# Power_Cond_2.net
KiCad netlist of a schematic drawn in EAGLE
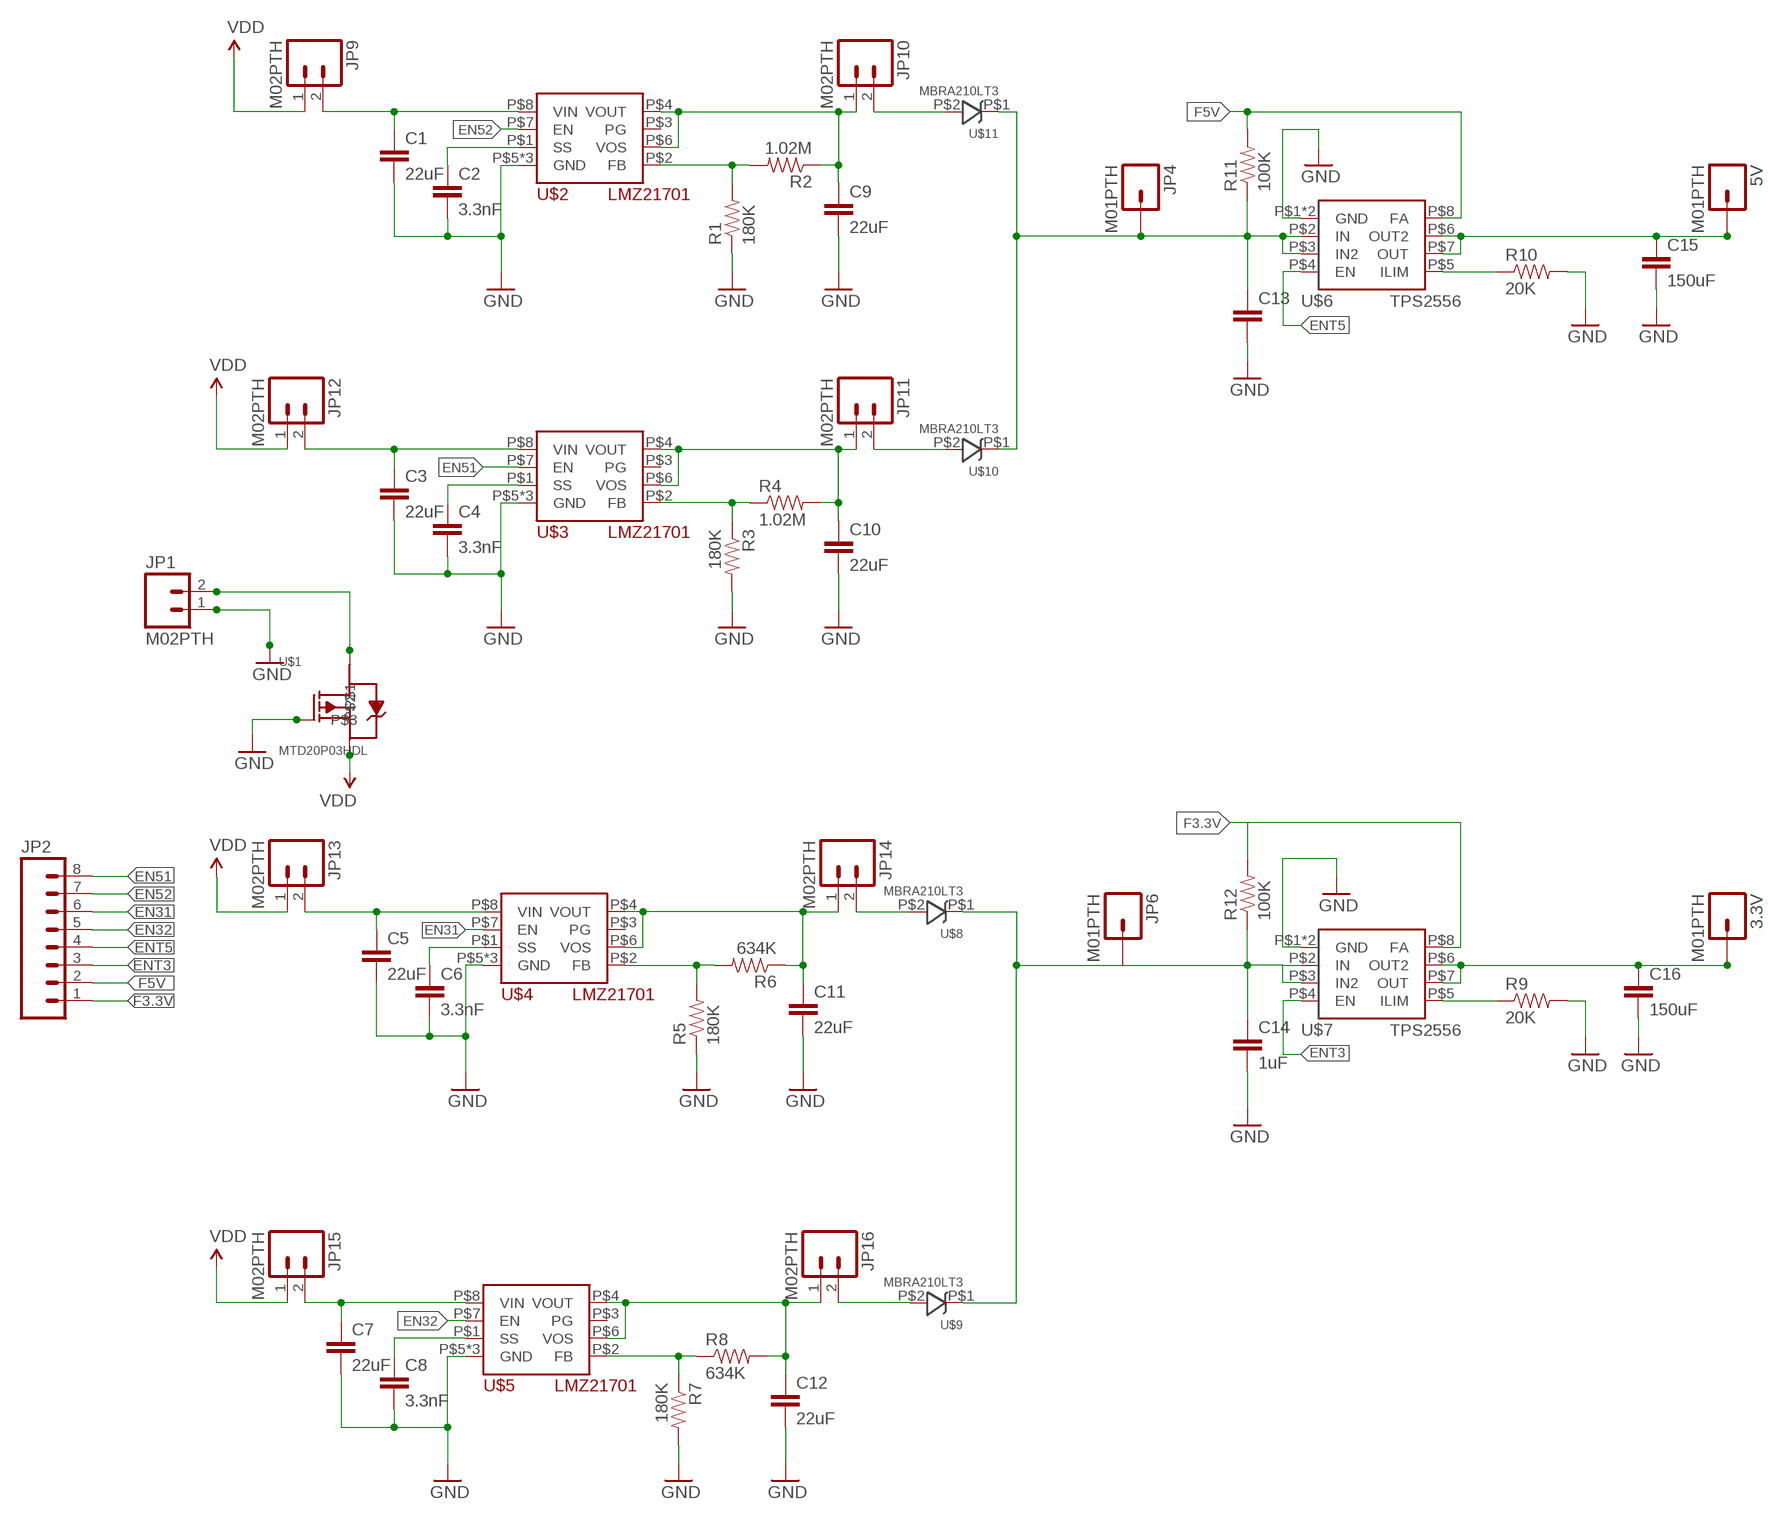
[diagram p0: schematic, sheet 1]

(export (version "E")
  (design (tool "Eeschema 10.0.6"))
  (components
    (comp (ref "3.3V")
      (value "M01PTH")
      (footprint "eagle-import:1X01")
      (libsource (lib "eagle-import") (part "M01PTH"))
    )
    (comp (ref "5V")
      (value "M01PTH")
      (footprint "eagle-import:1X01")
      (libsource (lib "eagle-import") (part "M01PTH"))
    )
    (comp (ref "C1")
      (value "22uF")
      (footprint "eagle-import:0603-CAP")
      (libsource (lib "eagle-import") (part "CAP0603-CAP"))
    )
    (comp (ref "C2")
      (value "3.3nF")
      (footprint "eagle-import:0603-CAP")
      (libsource (lib "eagle-import") (part "CAP0603-CAP"))
    )
    (comp (ref "C3")
      (value "22uF")
      (footprint "eagle-import:0603-CAP")
      (libsource (lib "eagle-import") (part "CAP0603-CAP"))
    )
    (comp (ref "C4")
      (value "3.3nF")
      (footprint "eagle-import:0603-CAP")
      (libsource (lib "eagle-import") (part "CAP0603-CAP"))
    )
    (comp (ref "C5")
      (value "22uF")
      (footprint "eagle-import:0603-CAP")
      (libsource (lib "eagle-import") (part "CAP0603-CAP"))
    )
    (comp (ref "C6")
      (value "3.3nF")
      (footprint "eagle-import:0603-CAP")
      (libsource (lib "eagle-import") (part "CAP0603-CAP"))
    )
    (comp (ref "C7")
      (value "22uF")
      (footprint "eagle-import:0603-CAP")
      (libsource (lib "eagle-import") (part "CAP0603-CAP"))
    )
    (comp (ref "C8")
      (value "3.3nF")
      (footprint "eagle-import:0603-CAP")
      (libsource (lib "eagle-import") (part "CAP0603-CAP"))
    )
    (comp (ref "C9")
      (value "22uF")
      (footprint "eagle-import:0603-CAP")
      (libsource (lib "eagle-import") (part "CAP0603-CAP"))
    )
    (comp (ref "C10")
      (value "22uF")
      (footprint "eagle-import:0603-CAP")
      (libsource (lib "eagle-import") (part "CAP0603-CAP"))
    )
    (comp (ref "C11")
      (value "22uF")
      (footprint "eagle-import:0603-CAP")
      (libsource (lib "eagle-import") (part "CAP0603-CAP"))
    )
    (comp (ref "C12")
      (value "22uF")
      (footprint "eagle-import:0603-CAP")
      (libsource (lib "eagle-import") (part "CAP0603-CAP"))
    )
    (comp (ref "C13")
      (value "CAP0603-CAP")
      (footprint "eagle-import:0603-CAP")
      (libsource (lib "eagle-import") (part "CAP0603-CAP"))
    )
    (comp (ref "C14")
      (value "1uF")
      (footprint "eagle-import:0603-CAP")
      (libsource (lib "eagle-import") (part "CAP0603-CAP"))
    )
    (comp (ref "C15")
      (value "150uF")
      (footprint "eagle-import:1206")
      (libsource (lib "eagle-import") (part "CAP1206"))
    )
    (comp (ref "C16")
      (value "150uF")
      (footprint "eagle-import:1206")
      (libsource (lib "eagle-import") (part "CAP1206"))
    )
    (comp (ref "JP1")
      (value "M02PTH")
      (footprint "eagle-import:1X02")
      (libsource (lib "eagle-import") (part "M02PTH"))
    )
    (comp (ref "JP2")
      (value "M08")
      (footprint "eagle-import:1X08_ROUND")
      (libsource (lib "eagle-import") (part "M08"))
    )
    (comp (ref "JP4")
      (value "M01PTH")
      (footprint "eagle-import:1X01")
      (libsource (lib "eagle-import") (part "M01PTH"))
    )
    (comp (ref "JP6")
      (value "M01PTH")
      (footprint "eagle-import:1X01")
      (libsource (lib "eagle-import") (part "M01PTH"))
    )
    (comp (ref "JP9")
      (value "M02PTH")
      (footprint "eagle-import:1X02")
      (libsource (lib "eagle-import") (part "M02PTH"))
    )
    (comp (ref "JP10")
      (value "M02PTH")
      (footprint "eagle-import:1X02")
      (libsource (lib "eagle-import") (part "M02PTH"))
    )
    (comp (ref "JP11")
      (value "M02PTH")
      (footprint "eagle-import:1X02")
      (libsource (lib "eagle-import") (part "M02PTH"))
    )
    (comp (ref "JP12")
      (value "M02PTH")
      (footprint "eagle-import:1X02")
      (libsource (lib "eagle-import") (part "M02PTH"))
    )
    (comp (ref "JP13")
      (value "M02PTH")
      (footprint "eagle-import:1X02")
      (libsource (lib "eagle-import") (part "M02PTH"))
    )
    (comp (ref "JP14")
      (value "M02PTH")
      (footprint "eagle-import:1X02")
      (libsource (lib "eagle-import") (part "M02PTH"))
    )
    (comp (ref "JP15")
      (value "M02PTH")
      (footprint "eagle-import:1X02")
      (libsource (lib "eagle-import") (part "M02PTH"))
    )
    (comp (ref "JP16")
      (value "M02PTH")
      (footprint "eagle-import:1X02")
      (libsource (lib "eagle-import") (part "M02PTH"))
    )
    (comp (ref "R1")
      (value "180K")
      (footprint "eagle-import:0603-RES")
      (libsource (lib "eagle-import") (part "RESISTOR0603-RES"))
    )
    (comp (ref "R2")
      (value "1.02M")
      (footprint "eagle-import:0603-RES")
      (libsource (lib "eagle-import") (part "RESISTOR0603-RES"))
    )
    (comp (ref "R3")
      (value "180K")
      (footprint "eagle-import:0603-RES")
      (libsource (lib "eagle-import") (part "RESISTOR0603-RES"))
    )
    (comp (ref "R4")
      (value "1.02M")
      (footprint "eagle-import:0603-RES")
      (libsource (lib "eagle-import") (part "RESISTOR0603-RES"))
    )
    (comp (ref "R5")
      (value "180K")
      (footprint "eagle-import:0603-RES")
      (libsource (lib "eagle-import") (part "RESISTOR0603-RES"))
    )
    (comp (ref "R6")
      (value "634K")
      (footprint "eagle-import:0603-RES")
      (libsource (lib "eagle-import") (part "RESISTOR0603-RES"))
    )
    (comp (ref "R7")
      (value "180K")
      (footprint "eagle-import:0603-RES")
      (libsource (lib "eagle-import") (part "RESISTOR0603-RES"))
    )
    (comp (ref "R8")
      (value "634K")
      (footprint "eagle-import:0603-RES")
      (libsource (lib "eagle-import") (part "RESISTOR0603-RES"))
    )
    (comp (ref "R9")
      (value "20K")
      (footprint "eagle-import:0603-RES")
      (libsource (lib "eagle-import") (part "RESISTOR0603-RES"))
    )
    (comp (ref "R10")
      (value "20K")
      (footprint "eagle-import:0603-RES")
      (libsource (lib "eagle-import") (part "RESISTOR0603-RES"))
    )
    (comp (ref "R11")
      (value "100K")
      (footprint "eagle-import:0603-RES")
      (libsource (lib "eagle-import") (part "RESISTOR0603-RES"))
    )
    (comp (ref "R12")
      (value "100K")
      (footprint "eagle-import:0603-RES")
      (libsource (lib "eagle-import") (part "RESISTOR0603-RES"))
    )
    (comp (ref "U$1")
      (value "MTD20P03HDL")
      (footprint "eagle-import:DPAK_369C_SMD")
      (libsource (lib "eagle-import") (part "MTD20P03HDL"))
    )
    (comp (ref "U$2")
      (value "LMZ21701")
      (footprint "eagle-import:LMZ21701")
      (libsource (lib "eagle-import") (part "LMZ21701"))
    )
    (comp (ref "U$3")
      (value "LMZ21701")
      (footprint "eagle-import:LMZ21701")
      (libsource (lib "eagle-import") (part "LMZ21701"))
    )
    (comp (ref "U$4")
      (value "LMZ21701")
      (footprint "eagle-import:LMZ21701")
      (libsource (lib "eagle-import") (part "LMZ21701"))
    )
    (comp (ref "U$5")
      (value "LMZ21701")
      (footprint "eagle-import:LMZ21701")
      (libsource (lib "eagle-import") (part "LMZ21701"))
    )
    (comp (ref "U$6")
      (value "TPS2556")
      (footprint "eagle-import:TPS2556")
      (libsource (lib "eagle-import") (part "TPS2556"))
    )
    (comp (ref "U$7")
      (value "TPS2556")
      (footprint "eagle-import:TPS2556")
      (libsource (lib "eagle-import") (part "TPS2556"))
    )
    (comp (ref "U$8")
      (value "MBRA210LT3")
      (footprint "eagle-import:DO-214AC-SMA")
      (libsource (lib "eagle-import") (part "MBRA210LT3"))
    )
    (comp (ref "U$9")
      (value "MBRA210LT3")
      (footprint "eagle-import:DO-214AC-SMA")
      (libsource (lib "eagle-import") (part "MBRA210LT3"))
    )
    (comp (ref "U$10")
      (value "MBRA210LT3")
      (footprint "eagle-import:DO-214AC-SMA")
      (libsource (lib "eagle-import") (part "MBRA210LT3"))
    )
    (comp (ref "U$11")
      (value "MBRA210LT3")
      (footprint "eagle-import:DO-214AC-SMA")
      (libsource (lib "eagle-import") (part "MBRA210LT3"))
    )
  )
  (nets
    (net (code "1") (name "/EN31") (class "Default")
      (node (ref "C5") (pin "1") (pinfunction "1_1") (pintype "passive"))
      (node (ref "JP13") (pin "2") (pinfunction "2_2") (pintype "passive"))
      (node (ref "JP2") (pin "6") (pinfunction "6_6") (pintype "passive"))
      (node (ref "U$4") (pin "P$7") (pinfunction "EN_P$7") (pintype "bidirectional"))
      (node (ref "U$4") (pin "P$8") (pinfunction "VIN_P$8") (pintype "bidirectional"))
    )
    (net (code "2") (name "/EN32") (class "Default")
      (node (ref "JP2") (pin "5") (pinfunction "5_5") (pintype "passive"))
      (node (ref "U$5") (pin "P$7") (pinfunction "EN_P$7") (pintype "bidirectional"))
    )
    (net (code "3") (name "/EN51") (class "Default")
      (node (ref "JP2") (pin "8") (pinfunction "8_8") (pintype "passive"))
      (node (ref "U$3") (pin "P$7") (pinfunction "EN_P$7") (pintype "bidirectional"))
    )
    (net (code "4") (name "/EN52") (class "Default")
      (node (ref "JP2") (pin "7") (pinfunction "7_7") (pintype "passive"))
      (node (ref "U$2") (pin "P$7") (pinfunction "EN_P$7") (pintype "bidirectional"))
    )
    (net (code "5") (name "/ENT3") (class "Default")
      (node (ref "JP2") (pin "3") (pinfunction "3_3") (pintype "passive"))
      (node (ref "U$7") (pin "P$4") (pinfunction "EN_P$4") (pintype "bidirectional"))
    )
    (net (code "6") (name "/ENT5") (class "Default")
      (node (ref "JP2") (pin "4") (pinfunction "4_4") (pintype "passive"))
      (node (ref "U$6") (pin "P$4") (pinfunction "EN_P$4") (pintype "bidirectional"))
    )
    (net (code "7") (name "/F3.3V") (class "Default")
      (node (ref "JP2") (pin "1") (pinfunction "1_1") (pintype "passive"))
      (node (ref "R12") (pin "2") (pinfunction "2_2") (pintype "passive"))
      (node (ref "U$7") (pin "P$8") (pinfunction "FA_P$8") (pintype "bidirectional"))
    )
    (net (code "8") (name "/F5V") (class "Default")
      (node (ref "JP2") (pin "2") (pinfunction "2_2") (pintype "passive"))
      (node (ref "R11") (pin "2") (pinfunction "2_2") (pintype "passive"))
      (node (ref "U$6") (pin "P$8") (pinfunction "FA_P$8") (pintype "bidirectional"))
    )
    (net (code "9") (name "GND") (class "Default")
      (node (ref "C1") (pin "2") (pinfunction "2_2") (pintype "passive"))
      (node (ref "C10") (pin "2") (pinfunction "2_2") (pintype "passive"))
      (node (ref "C11") (pin "2") (pinfunction "2_2") (pintype "passive"))
      (node (ref "C12") (pin "2") (pinfunction "2_2") (pintype "passive"))
      (node (ref "C13") (pin "2") (pinfunction "2_2") (pintype "passive"))
      (node (ref "C14") (pin "2") (pinfunction "2_2") (pintype "passive"))
      (node (ref "C15") (pin "2") (pinfunction "2_2") (pintype "passive"))
      (node (ref "C16") (pin "2") (pinfunction "2_2") (pintype "passive"))
      (node (ref "C2") (pin "2") (pinfunction "2_2") (pintype "passive"))
      (node (ref "C3") (pin "2") (pinfunction "2_2") (pintype "passive"))
      (node (ref "C4") (pin "2") (pinfunction "2_2") (pintype "passive"))
      (node (ref "C5") (pin "2") (pinfunction "2_2") (pintype "passive"))
      (node (ref "C6") (pin "2") (pinfunction "2_2") (pintype "passive"))
      (node (ref "C7") (pin "2") (pinfunction "2_2") (pintype "passive"))
      (node (ref "C8") (pin "2") (pinfunction "2_2") (pintype "passive"))
      (node (ref "C9") (pin "2") (pinfunction "2_2") (pintype "passive"))
      (node (ref "JP1") (pin "1") (pinfunction "1_1") (pintype "passive"))
      (node (ref "R1") (pin "1") (pinfunction "1_1") (pintype "passive"))
      (node (ref "R10") (pin "2") (pinfunction "2_2") (pintype "passive"))
      (node (ref "R3") (pin "2") (pinfunction "2_2") (pintype "passive"))
      (node (ref "R5") (pin "1") (pinfunction "1_1") (pintype "passive"))
      (node (ref "R7") (pin "2") (pinfunction "2_2") (pintype "passive"))
      (node (ref "R9") (pin "2") (pinfunction "2_2") (pintype "passive"))
      (node (ref "U$1") (pin "P$3") (pinfunction "P$3_P$3") (pintype "bidirectional"))
      (node (ref "U$2") (pin "P$10") (pinfunction "GND_P$10") (pintype "bidirectional"))
      (node (ref "U$2") (pin "P$5") (pinfunction "GND_P$5") (pintype "bidirectional"))
      (node (ref "U$2") (pin "P$9") (pinfunction "GND_P$9") (pintype "bidirectional"))
      (node (ref "U$3") (pin "P$10") (pinfunction "GND_P$10") (pintype "bidirectional"))
      (node (ref "U$3") (pin "P$5") (pinfunction "GND_P$5") (pintype "bidirectional"))
      (node (ref "U$3") (pin "P$9") (pinfunction "GND_P$9") (pintype "bidirectional"))
      (node (ref "U$4") (pin "P$10") (pinfunction "GND_P$10") (pintype "bidirectional"))
      (node (ref "U$4") (pin "P$5") (pinfunction "GND_P$5") (pintype "bidirectional"))
      (node (ref "U$4") (pin "P$9") (pinfunction "GND_P$9") (pintype "bidirectional"))
      (node (ref "U$5") (pin "P$10") (pinfunction "GND_P$10") (pintype "bidirectional"))
      (node (ref "U$5") (pin "P$5") (pinfunction "GND_P$5") (pintype "bidirectional"))
      (node (ref "U$5") (pin "P$9") (pinfunction "GND_P$9") (pintype "bidirectional"))
      (node (ref "U$6") (pin "P$1") (pinfunction "GND_P$1") (pintype "bidirectional"))
      (node (ref "U$6") (pin "P$9") (pinfunction "GND_P$9") (pintype "bidirectional"))
      (node (ref "U$7") (pin "P$1") (pinfunction "GND_P$1") (pintype "bidirectional"))
      (node (ref "U$7") (pin "P$9") (pinfunction "GND_P$9") (pintype "bidirectional"))
    )
    (net (code "10") (name "Net-(JP10-Pad2)") (class "Default")
      (node (ref "JP10") (pin "2") (pinfunction "2_2") (pintype "passive"))
      (node (ref "U$11") (pin "P$2") (pinfunction "P$2_P$2") (pintype "bidirectional"))
    )
    (net (code "11") (name "Net-(JP11-Pad2)") (class "Default")
      (node (ref "JP11") (pin "2") (pinfunction "2_2") (pintype "passive"))
      (node (ref "U$10") (pin "P$2") (pinfunction "P$2_P$2") (pintype "bidirectional"))
    )
    (net (code "12") (name "Net-(JP14-Pad2)") (class "Default")
      (node (ref "JP14") (pin "2") (pinfunction "2_2") (pintype "passive"))
      (node (ref "U$8") (pin "P$2") (pinfunction "P$2_P$2") (pintype "bidirectional"))
    )
    (net (code "13") (name "Net-(JP16-Pad2)") (class "Default")
      (node (ref "JP16") (pin "2") (pinfunction "2_2") (pintype "passive"))
      (node (ref "U$9") (pin "P$2") (pinfunction "P$2_P$2") (pintype "bidirectional"))
    )
    (net (code "14") (name "Net-(U$2-FB)") (class "Default")
      (node (ref "R1") (pin "2") (pinfunction "2_2") (pintype "passive"))
      (node (ref "R2") (pin "2") (pinfunction "2_2") (pintype "passive"))
      (node (ref "U$2") (pin "P$2") (pinfunction "FB_P$2") (pintype "bidirectional"))
    )
    (net (code "15") (name "Net-(U$2-SS)") (class "Default")
      (node (ref "C2") (pin "1") (pinfunction "1_1") (pintype "passive"))
      (node (ref "U$2") (pin "P$1") (pinfunction "SS_P$1") (pintype "bidirectional"))
    )
    (net (code "16") (name "Net-(U$2-VIN)") (class "Default")
      (node (ref "C1") (pin "1") (pinfunction "1_1") (pintype "passive"))
      (node (ref "JP9") (pin "2") (pinfunction "2_2") (pintype "passive"))
      (node (ref "U$2") (pin "P$8") (pinfunction "VIN_P$8") (pintype "bidirectional"))
    )
    (net (code "17") (name "Net-(U$2-VOS)") (class "Default")
      (node (ref "C9") (pin "1") (pinfunction "1_1") (pintype "passive"))
      (node (ref "JP10") (pin "1") (pinfunction "1_1") (pintype "passive"))
      (node (ref "R2") (pin "1") (pinfunction "1_1") (pintype "passive"))
      (node (ref "U$2") (pin "P$4") (pinfunction "VOUT_P$4") (pintype "bidirectional"))
      (node (ref "U$2") (pin "P$6") (pinfunction "VOS_P$6") (pintype "bidirectional"))
    )
    (net (code "18") (name "Net-(U$3-FB)") (class "Default")
      (node (ref "R3") (pin "1") (pinfunction "1_1") (pintype "passive"))
      (node (ref "R4") (pin "1") (pinfunction "1_1") (pintype "passive"))
      (node (ref "U$3") (pin "P$2") (pinfunction "FB_P$2") (pintype "bidirectional"))
    )
    (net (code "19") (name "Net-(U$3-SS)") (class "Default")
      (node (ref "C4") (pin "1") (pinfunction "1_1") (pintype "passive"))
      (node (ref "U$3") (pin "P$1") (pinfunction "SS_P$1") (pintype "bidirectional"))
    )
    (net (code "20") (name "Net-(U$3-VIN)") (class "Default")
      (node (ref "C3") (pin "1") (pinfunction "1_1") (pintype "passive"))
      (node (ref "JP12") (pin "2") (pinfunction "2_2") (pintype "passive"))
      (node (ref "U$3") (pin "P$8") (pinfunction "VIN_P$8") (pintype "bidirectional"))
    )
    (net (code "21") (name "Net-(U$3-VOS)") (class "Default")
      (node (ref "C10") (pin "1") (pinfunction "1_1") (pintype "passive"))
      (node (ref "JP11") (pin "1") (pinfunction "1_1") (pintype "passive"))
      (node (ref "R4") (pin "2") (pinfunction "2_2") (pintype "passive"))
      (node (ref "U$3") (pin "P$4") (pinfunction "VOUT_P$4") (pintype "bidirectional"))
      (node (ref "U$3") (pin "P$6") (pinfunction "VOS_P$6") (pintype "bidirectional"))
    )
    (net (code "22") (name "Net-(U$4-FB)") (class "Default")
      (node (ref "R5") (pin "2") (pinfunction "2_2") (pintype "passive"))
      (node (ref "R6") (pin "2") (pinfunction "2_2") (pintype "passive"))
      (node (ref "U$4") (pin "P$2") (pinfunction "FB_P$2") (pintype "bidirectional"))
    )
    (net (code "23") (name "Net-(U$4-SS)") (class "Default")
      (node (ref "C6") (pin "1") (pinfunction "1_1") (pintype "passive"))
      (node (ref "U$4") (pin "P$1") (pinfunction "SS_P$1") (pintype "bidirectional"))
    )
    (net (code "24") (name "Net-(U$4-VOS)") (class "Default")
      (node (ref "C11") (pin "1") (pinfunction "1_1") (pintype "passive"))
      (node (ref "JP14") (pin "1") (pinfunction "1_1") (pintype "passive"))
      (node (ref "R6") (pin "1") (pinfunction "1_1") (pintype "passive"))
      (node (ref "U$4") (pin "P$4") (pinfunction "VOUT_P$4") (pintype "bidirectional"))
      (node (ref "U$4") (pin "P$6") (pinfunction "VOS_P$6") (pintype "bidirectional"))
    )
    (net (code "25") (name "Net-(U$5-FB)") (class "Default")
      (node (ref "R7") (pin "1") (pinfunction "1_1") (pintype "passive"))
      (node (ref "R8") (pin "1") (pinfunction "1_1") (pintype "passive"))
      (node (ref "U$5") (pin "P$2") (pinfunction "FB_P$2") (pintype "bidirectional"))
    )
    (net (code "26") (name "Net-(U$5-SS)") (class "Default")
      (node (ref "C8") (pin "1") (pinfunction "1_1") (pintype "passive"))
      (node (ref "U$5") (pin "P$1") (pinfunction "SS_P$1") (pintype "bidirectional"))
    )
    (net (code "27") (name "Net-(U$5-VIN)") (class "Default")
      (node (ref "C7") (pin "1") (pinfunction "1_1") (pintype "passive"))
      (node (ref "JP15") (pin "2") (pinfunction "2_2") (pintype "passive"))
      (node (ref "U$5") (pin "P$8") (pinfunction "VIN_P$8") (pintype "bidirectional"))
    )
    (net (code "28") (name "Net-(U$5-VOS)") (class "Default")
      (node (ref "C12") (pin "1") (pinfunction "1_1") (pintype "passive"))
      (node (ref "JP16") (pin "1") (pinfunction "1_1") (pintype "passive"))
      (node (ref "R8") (pin "2") (pinfunction "2_2") (pintype "passive"))
      (node (ref "U$5") (pin "P$4") (pinfunction "VOUT_P$4") (pintype "bidirectional"))
      (node (ref "U$5") (pin "P$6") (pinfunction "VOS_P$6") (pintype "bidirectional"))
    )
    (net (code "29") (name "Net-(U$6-ILIM)") (class "Default")
      (node (ref "R10") (pin "1") (pinfunction "1_1") (pintype "passive"))
      (node (ref "U$6") (pin "P$5") (pinfunction "ILIM_P$5") (pintype "bidirectional"))
    )
    (net (code "30") (name "Net-(U$6-IN)") (class "Default")
      (node (ref "C13") (pin "1") (pinfunction "1_1") (pintype "passive"))
      (node (ref "JP4") (pin "1") (pinfunction "1_1") (pintype "passive"))
      (node (ref "R11") (pin "1") (pinfunction "1_1") (pintype "passive"))
      (node (ref "U$10") (pin "P$1") (pinfunction "P$1_P$1") (pintype "bidirectional"))
      (node (ref "U$11") (pin "P$1") (pinfunction "P$1_P$1") (pintype "bidirectional"))
      (node (ref "U$6") (pin "P$2") (pinfunction "IN_P$2") (pintype "bidirectional"))
      (node (ref "U$6") (pin "P$3") (pinfunction "IN2_P$3") (pintype "bidirectional"))
    )
    (net (code "31") (name "Net-(U$6-OUT)") (class "Default")
      (node (ref "5V") (pin "1") (pinfunction "1_1") (pintype "passive"))
      (node (ref "C15") (pin "1") (pinfunction "1_1") (pintype "passive"))
      (node (ref "U$6") (pin "P$6") (pinfunction "OUT2_P$6") (pintype "bidirectional"))
      (node (ref "U$6") (pin "P$7") (pinfunction "OUT_P$7") (pintype "bidirectional"))
    )
    (net (code "32") (name "Net-(U$7-ILIM)") (class "Default")
      (node (ref "R9") (pin "1") (pinfunction "1_1") (pintype "passive"))
      (node (ref "U$7") (pin "P$5") (pinfunction "ILIM_P$5") (pintype "bidirectional"))
    )
    (net (code "33") (name "Net-(U$7-IN)") (class "Default")
      (node (ref "C14") (pin "1") (pinfunction "1_1") (pintype "passive"))
      (node (ref "R12") (pin "1") (pinfunction "1_1") (pintype "passive"))
      (node (ref "U$7") (pin "P$2") (pinfunction "IN_P$2") (pintype "bidirectional"))
      (node (ref "U$7") (pin "P$3") (pinfunction "IN2_P$3") (pintype "bidirectional"))
      (node (ref "U$8") (pin "P$1") (pinfunction "P$1_P$1") (pintype "bidirectional"))
      (node (ref "U$9") (pin "P$1") (pinfunction "P$1_P$1") (pintype "bidirectional"))
    )
    (net (code "34") (name "Net-(U$7-OUT)") (class "Default")
      (node (ref "3.3V") (pin "1") (pinfunction "1_1") (pintype "passive"))
      (node (ref "C16") (pin "1") (pinfunction "1_1") (pintype "passive"))
      (node (ref "U$7") (pin "P$6") (pinfunction "OUT2_P$6") (pintype "bidirectional"))
      (node (ref "U$7") (pin "P$7") (pinfunction "OUT_P$7") (pintype "bidirectional"))
    )
    (net (code "35") (name "VDD") (class "Default")
      (node (ref "JP12") (pin "1") (pinfunction "1_1") (pintype "passive"))
      (node (ref "JP13") (pin "1") (pinfunction "1_1") (pintype "passive"))
      (node (ref "JP15") (pin "1") (pinfunction "1_1") (pintype "passive"))
      (node (ref "JP9") (pin "1") (pinfunction "1_1") (pintype "passive"))
    )
    (net (code "36") (name "unconnected-(JP1-Pad2)") (class "Default")
      (node (ref "JP1") (pin "2") (pinfunction "2_2") (pintype "passive"))
    )
    (net (code "37") (name "unconnected-(JP6-Pad1)") (class "Default")
      (node (ref "JP6") (pin "1") (pinfunction "1_1") (pintype "passive"))
    )
    (net (code "38") (name "unconnected-(U$1-PadP$1)") (class "Default")
      (node (ref "U$1") (pin "P$1") (pinfunction "P$1_P$1") (pintype "bidirectional"))
    )
    (net (code "39") (name "unconnected-(U$1-PadP$2)") (class "Default")
      (node (ref "U$1") (pin "P$2") (pinfunction "P$2_P$2") (pintype "bidirectional"))
    )
    (net (code "40") (name "unconnected-(U$2-PG-PadP$3)") (class "Default")
      (node (ref "U$2") (pin "P$3") (pinfunction "PG_P$3") (pintype "bidirectional"))
    )
    (net (code "41") (name "unconnected-(U$3-PG-PadP$3)") (class "Default")
      (node (ref "U$3") (pin "P$3") (pinfunction "PG_P$3") (pintype "bidirectional"))
    )
    (net (code "42") (name "unconnected-(U$4-PG-PadP$3)") (class "Default")
      (node (ref "U$4") (pin "P$3") (pinfunction "PG_P$3") (pintype "bidirectional"))
    )
    (net (code "43") (name "unconnected-(U$5-PG-PadP$3)") (class "Default")
      (node (ref "U$5") (pin "P$3") (pinfunction "PG_P$3") (pintype "bidirectional"))
    )
  )
)
